# wristband.net
KiCad netlist of a schematic drawn in EAGLE
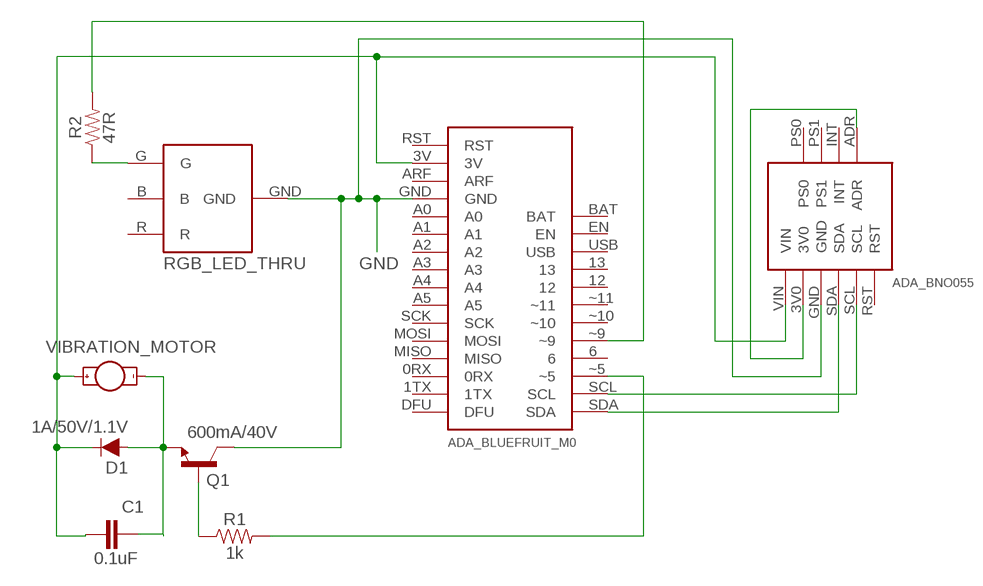
[diagram p0: schematic, sheet 1]

(export (version "E")
  (design (tool "Eeschema 10.0.6"))
  (components
    (comp (ref "BF1")
      (value "ADA_BLUEFRUIT_M0")
      (footprint "eagle-import:ADA_BLUEFRUIT_M0")
      (libsource (lib "eagle-import") (part "ADA_BLUEFRUIT_M0"))
    )
    (comp (ref "BNO1")
      (value "ADA_BNO055")
      (footprint "eagle-import:ADA_BNO055")
      (libsource (lib "eagle-import") (part "ADA_BNO055"))
    )
    (comp (ref "C1")
      (value "0.1uF")
      (footprint "eagle-import:CAP-PTH-SMALL-KIT")
      (libsource (lib "eagle-import") (part "0.1UF-KIT-EZ-50V-20%"))
    )
    (comp (ref "D1")
      (value "1A/50V/1.1V")
      (footprint "eagle-import:DIODE-1N4001")
      (libsource (lib "eagle-import") (part "DIODE-PTH"))
    )
    (comp (ref "Q1")
      (value "600mA/40V")
      (footprint "eagle-import:TO-92")
      (libsource (lib "eagle-import") (part "TRANS_NPN-P2N2222A"))
    )
    (comp (ref "R1")
      (value "1k")
      (footprint "eagle-import:AXIAL-0.3")
      (libsource (lib "eagle-import") (part "1KOHM-HORIZ-1/4W-1%"))
    )
    (comp (ref "R2")
      (value "47R")
      (footprint "eagle-import:AXIAL-0.3")
      (libsource (lib "eagle-import") (part "1KOHM-HORIZ-1/4W-1%"))
    )
    (comp (ref "RGB_LED1")
      (value "RGB_LED_THRU")
      (footprint "eagle-import:RGB_LEB_RGB_2")
      (libsource (lib "eagle-import") (part "RGB_LED_THRU"))
    )
    (comp (ref "U$1")
      (value "VIBRATION_MOTOR")
      (footprint "eagle-import:VIBRATION_MOTOR")
      (libsource (lib "eagle-import") (part "VIBRATION_MOTOR"))
    )
  )
  (nets
    (net (code "1") (name "/GND") (class "Default")
      (node (ref "BF1") (pin "GND") (pinfunction "GND_GND") (pintype "bidirectional"))
      (node (ref "BNO1") (pin "GND") (pinfunction "GND_GND") (pintype "bidirectional"))
      (node (ref "Q1") (pin "1") (pinfunction "C_1") (pintype "passive"))
      (node (ref "RGB_LED1") (pin "GND") (pinfunction "GND_GND") (pintype "bidirectional"))
    )
    (net (code "2") (name "Net-(BF1-Pad3V)") (class "Default")
      (node (ref "BF1") (pin "3V") (pinfunction "3V_3V") (pintype "bidirectional"))
      (node (ref "BNO1") (pin "VIN") (pinfunction "VIN_VIN") (pintype "bidirectional"))
      (node (ref "C1") (pin "1") (pinfunction "1_1") (pintype "passive"))
      (node (ref "D1") (pin "C") (pinfunction "C_C") (pintype "passive"))
      (node (ref "U$1") (pin "+") (pinfunction "+_+") (pintype "bidirectional"))
    )
    (net (code "3") (name "Net-(BF1-PadSCL)") (class "Default")
      (node (ref "BF1") (pin "SCL") (pinfunction "SCL_SCL") (pintype "bidirectional"))
      (node (ref "BNO1") (pin "SCL") (pinfunction "SCL_SCL") (pintype "bidirectional"))
    )
    (net (code "4") (name "Net-(BF1-PadSDA)") (class "Default")
      (node (ref "BF1") (pin "SDA") (pinfunction "SDA_SDA") (pintype "bidirectional"))
      (node (ref "BNO1") (pin "SDA") (pinfunction "SDA_SDA") (pintype "bidirectional"))
    )
    (net (code "5") (name "Net-(BF1-~{5})") (class "Default")
      (node (ref "BF1") (pin "~5") (pinfunction "~{5}_~5") (pintype "bidirectional"))
      (node (ref "R1") (pin "P$2") (pinfunction "2_P$2") (pintype "passive"))
    )
    (net (code "6") (name "Net-(BF1-~{9})") (class "Default")
      (node (ref "BF1") (pin "~9") (pinfunction "~{9}_~9") (pintype "bidirectional"))
      (node (ref "R2") (pin "P$2") (pinfunction "2_P$2") (pintype "passive"))
    )
    (net (code "7") (name "Net-(BNO1-Pad3V0)") (class "Default")
      (node (ref "BNO1") (pin "3V0") (pinfunction "3V0_3V0") (pintype "bidirectional"))
      (node (ref "BNO1") (pin "ADR") (pinfunction "ADR_ADR") (pintype "bidirectional"))
    )
    (net (code "8") (name "Net-(Q1-B)") (class "Default")
      (node (ref "Q1") (pin "2") (pinfunction "B_2") (pintype "passive"))
      (node (ref "R1") (pin "P$1") (pinfunction "1_P$1") (pintype "passive"))
    )
    (net (code "9") (name "Net-(Q1-E)") (class "Default")
      (node (ref "C1") (pin "2") (pinfunction "2_2") (pintype "passive"))
      (node (ref "D1") (pin "A") (pinfunction "A_A") (pintype "passive"))
      (node (ref "Q1") (pin "3") (pinfunction "E_3") (pintype "passive"))
      (node (ref "U$1") (pin "-") (pinfunction "-_-") (pintype "bidirectional"))
    )
    (net (code "10") (name "Net-(R2-1)") (class "Default")
      (node (ref "R2") (pin "P$1") (pinfunction "1_P$1") (pintype "passive"))
      (node (ref "RGB_LED1") (pin "G") (pinfunction "G_G") (pintype "bidirectional"))
    )
    (net (code "11") (name "unconnected-(BF1-Pad0RX)") (class "Default")
      (node (ref "BF1") (pin "0RX") (pinfunction "0RX_0RX") (pintype "bidirectional"))
    )
    (net (code "12") (name "unconnected-(BF1-Pad1TX)") (class "Default")
      (node (ref "BF1") (pin "1TX") (pinfunction "1TX_1TX") (pintype "bidirectional"))
    )
    (net (code "13") (name "unconnected-(BF1-Pad6)") (class "Default")
      (node (ref "BF1") (pin "6") (pinfunction "6_6") (pintype "bidirectional"))
    )
    (net (code "14") (name "unconnected-(BF1-Pad12)") (class "Default")
      (node (ref "BF1") (pin "12") (pinfunction "12_12") (pintype "bidirectional"))
    )
    (net (code "15") (name "unconnected-(BF1-Pad13)") (class "Default")
      (node (ref "BF1") (pin "13") (pinfunction "13_13") (pintype "bidirectional"))
    )
    (net (code "16") (name "unconnected-(BF1-PadA0)") (class "Default")
      (node (ref "BF1") (pin "A0") (pinfunction "A0_A0") (pintype "bidirectional"))
    )
    (net (code "17") (name "unconnected-(BF1-PadA1)") (class "Default")
      (node (ref "BF1") (pin "A1") (pinfunction "A1_A1") (pintype "bidirectional"))
    )
    (net (code "18") (name "unconnected-(BF1-PadA2)") (class "Default")
      (node (ref "BF1") (pin "A2") (pinfunction "A2_A2") (pintype "bidirectional"))
    )
    (net (code "19") (name "unconnected-(BF1-PadA3)") (class "Default")
      (node (ref "BF1") (pin "A3") (pinfunction "A3_A3") (pintype "bidirectional"))
    )
    (net (code "20") (name "unconnected-(BF1-PadA4)") (class "Default")
      (node (ref "BF1") (pin "A4") (pinfunction "A4_A4") (pintype "bidirectional"))
    )
    (net (code "21") (name "unconnected-(BF1-PadA5)") (class "Default")
      (node (ref "BF1") (pin "A5") (pinfunction "A5_A5") (pintype "bidirectional"))
    )
    (net (code "22") (name "unconnected-(BF1-PadARF)") (class "Default")
      (node (ref "BF1") (pin "ARF") (pinfunction "ARF_ARF") (pintype "bidirectional"))
    )
    (net (code "23") (name "unconnected-(BF1-PadBAT)") (class "Default")
      (node (ref "BF1") (pin "BAT") (pinfunction "BAT_BAT") (pintype "bidirectional"))
    )
    (net (code "24") (name "unconnected-(BF1-PadDFU)") (class "Default")
      (node (ref "BF1") (pin "DFU") (pinfunction "DFU_DFU") (pintype "bidirectional"))
    )
    (net (code "25") (name "unconnected-(BF1-PadEN)") (class "Default")
      (node (ref "BF1") (pin "EN") (pinfunction "EN_EN") (pintype "bidirectional"))
    )
    (net (code "26") (name "unconnected-(BF1-PadMISO)") (class "Default")
      (node (ref "BF1") (pin "MISO") (pinfunction "MISO_MISO") (pintype "bidirectional"))
    )
    (net (code "27") (name "unconnected-(BF1-PadMOSI)") (class "Default")
      (node (ref "BF1") (pin "MOSI") (pinfunction "MOSI_MOSI") (pintype "bidirectional"))
    )
    (net (code "28") (name "unconnected-(BF1-PadRST)") (class "Default")
      (node (ref "BF1") (pin "RST") (pinfunction "RST_RST") (pintype "bidirectional"))
    )
    (net (code "29") (name "unconnected-(BF1-PadSCK)") (class "Default")
      (node (ref "BF1") (pin "SCK") (pinfunction "SCK_SCK") (pintype "bidirectional"))
    )
    (net (code "30") (name "unconnected-(BF1-PadUSB)") (class "Default")
      (node (ref "BF1") (pin "USB") (pinfunction "USB_USB") (pintype "bidirectional"))
    )
    (net (code "31") (name "unconnected-(BF1-~{10}-Pad~10)") (class "Default")
      (node (ref "BF1") (pin "~10") (pinfunction "~{10}_~10") (pintype "bidirectional"))
    )
    (net (code "32") (name "unconnected-(BF1-~{11}-Pad~11)") (class "Default")
      (node (ref "BF1") (pin "~11") (pinfunction "~{11}_~11") (pintype "bidirectional"))
    )
    (net (code "33") (name "unconnected-(BNO1-PadINT)") (class "Default")
      (node (ref "BNO1") (pin "INT") (pinfunction "INT_INT") (pintype "bidirectional"))
    )
    (net (code "34") (name "unconnected-(BNO1-PadPS0)") (class "Default")
      (node (ref "BNO1") (pin "PS0") (pinfunction "PS0_PS0") (pintype "bidirectional"))
    )
    (net (code "35") (name "unconnected-(BNO1-PadPS1)") (class "Default")
      (node (ref "BNO1") (pin "PS1") (pinfunction "PS1_PS1") (pintype "bidirectional"))
    )
    (net (code "36") (name "unconnected-(BNO1-PadRST)") (class "Default")
      (node (ref "BNO1") (pin "RST") (pinfunction "RST_RST") (pintype "bidirectional"))
    )
    (net (code "37") (name "unconnected-(RGB_LED1-PadB)") (class "Default")
      (node (ref "RGB_LED1") (pin "B") (pinfunction "B_B") (pintype "bidirectional"))
    )
    (net (code "38") (name "unconnected-(RGB_LED1-PadR)") (class "Default")
      (node (ref "RGB_LED1") (pin "R") (pinfunction "R_R") (pintype "bidirectional"))
    )
  )
)
